# StearnsMTvrs.net
KiCad netlist of a schematic drawn in EAGLE
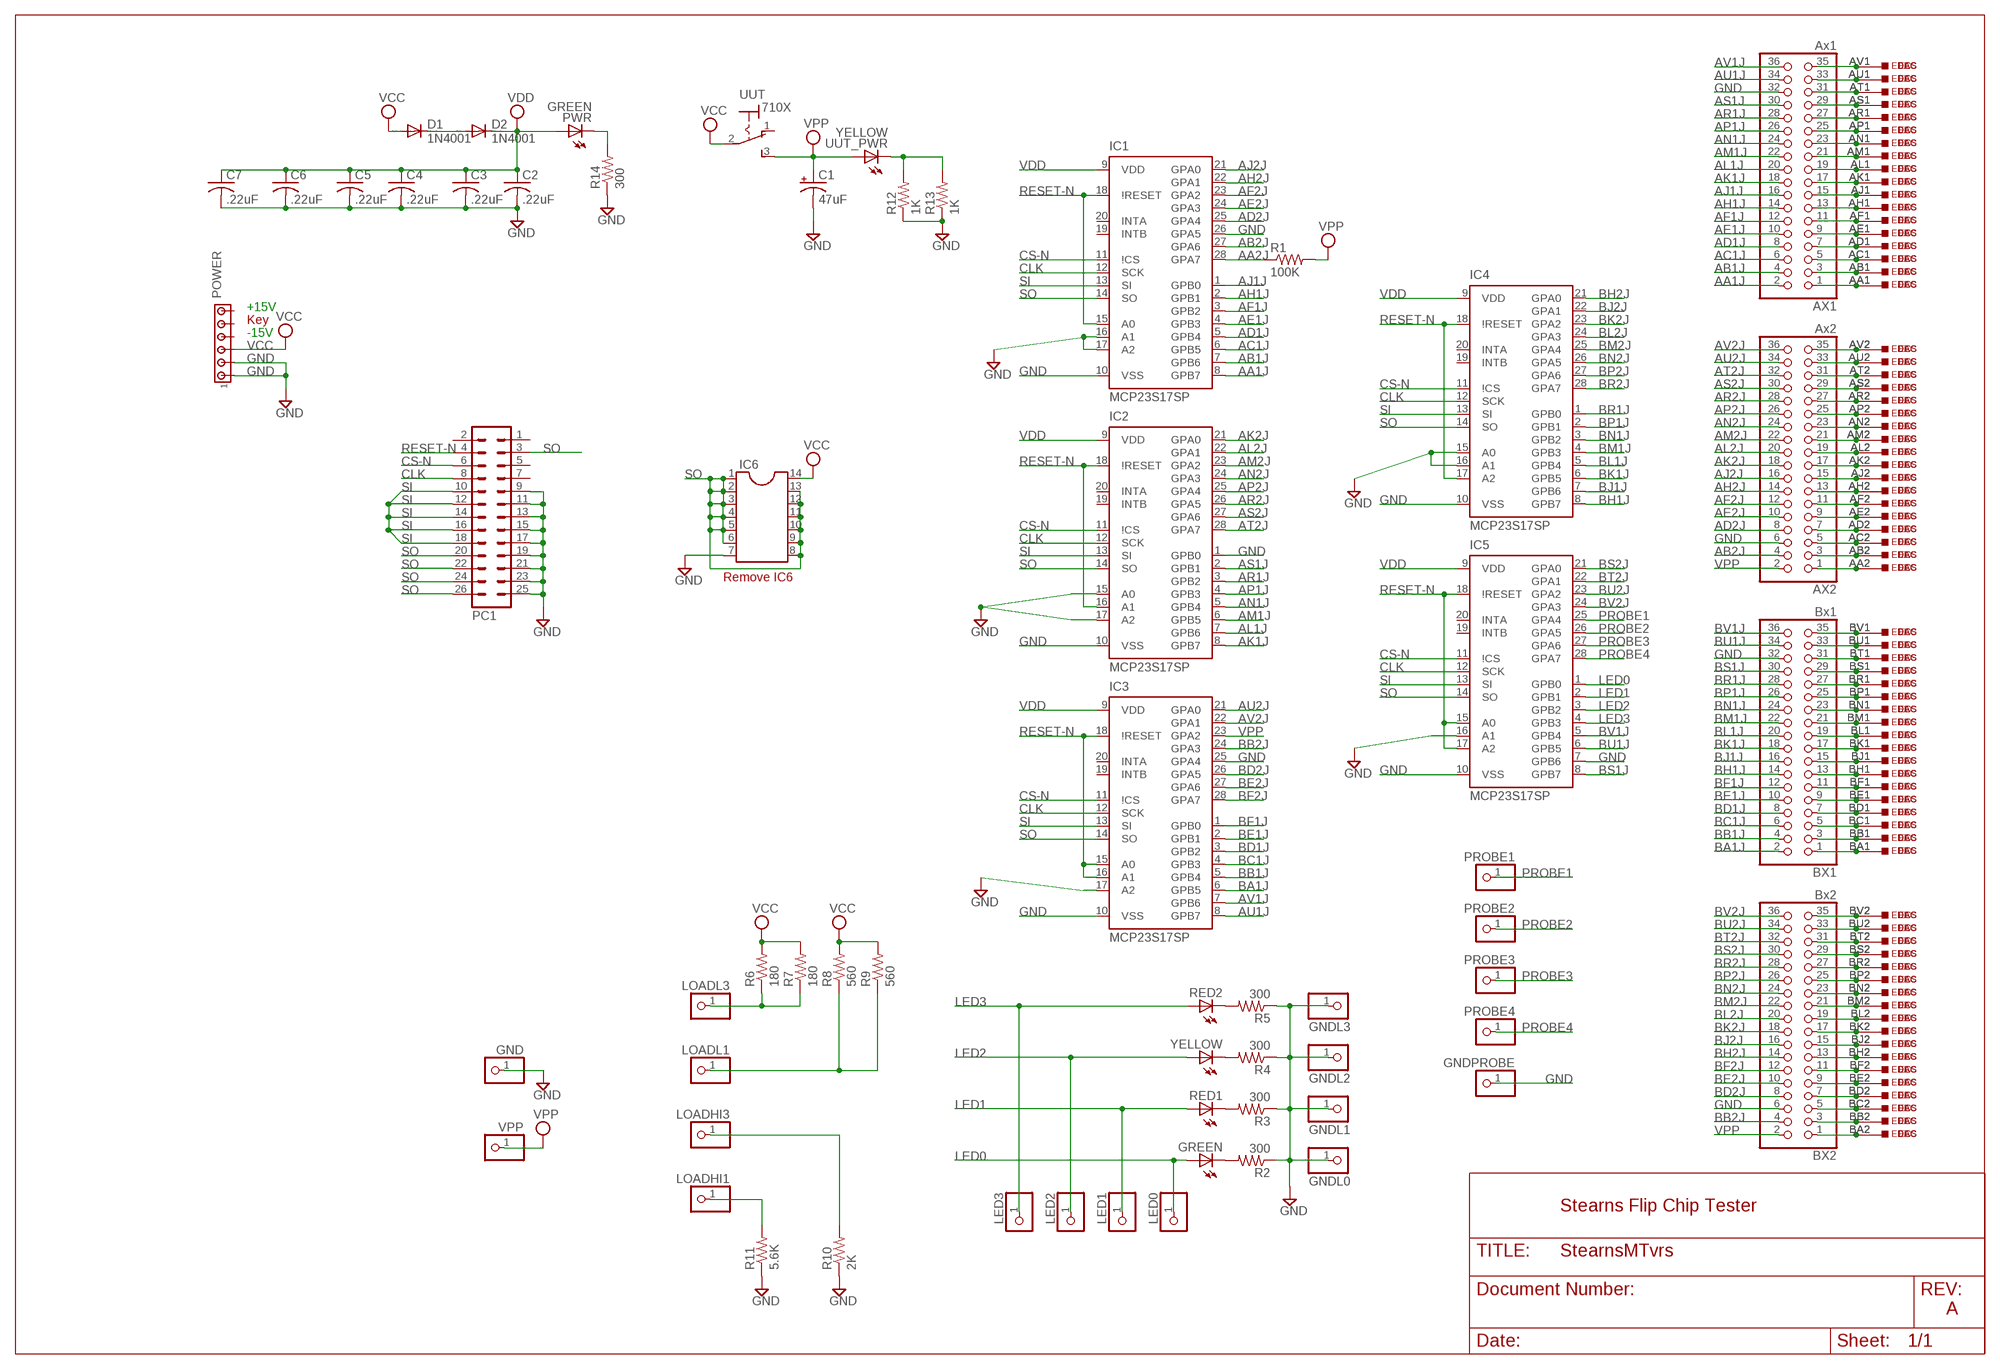
[diagram p0: schematic, sheet 1]

(export (version "E")
  (design (tool "Eeschema 10.0.6"))
  (components
    (comp (ref "AX1")
      (value "Ax1")
      (footprint "eagle-import:2X18")
      (libsource (lib "eagle-import") (part "PINHD-2X18"))
    )
    (comp (ref "AX2")
      (value "Ax2")
      (footprint "eagle-import:2X18")
      (libsource (lib "eagle-import") (part "PINHD-2X18"))
    )
    (comp (ref "BX1")
      (value "Bx1")
      (footprint "eagle-import:2X18")
      (libsource (lib "eagle-import") (part "PINHD-2X18"))
    )
    (comp (ref "BX2")
      (value "Bx2")
      (footprint "eagle-import:2X18")
      (libsource (lib "eagle-import") (part "PINHD-2X18"))
    )
    (comp (ref "C1")
      (value "47uF")
      (footprint "eagle-import:E5-8,5")
      (libsource (lib "eagle-import") (part "CPOL-USE5-8.5"))
    )
    (comp (ref "C2")
      (value ".22uF")
      (footprint "eagle-import:C050-025X075")
      (libsource (lib "eagle-import") (part "C-US050-025X075"))
    )
    (comp (ref "C3")
      (value ".22uF")
      (footprint "eagle-import:C050-025X075")
      (libsource (lib "eagle-import") (part "C-US050-025X075"))
    )
    (comp (ref "C4")
      (value ".22uF")
      (footprint "eagle-import:C050-025X075")
      (libsource (lib "eagle-import") (part "C-US050-025X075"))
    )
    (comp (ref "C5")
      (value ".22uF")
      (footprint "eagle-import:C050-025X075")
      (libsource (lib "eagle-import") (part "C-US050-025X075"))
    )
    (comp (ref "C6")
      (value ".22uF")
      (footprint "eagle-import:C050-025X075")
      (libsource (lib "eagle-import") (part "C-US050-025X075"))
    )
    (comp (ref "C7")
      (value ".22uF")
      (footprint "eagle-import:C050-025X075")
      (libsource (lib "eagle-import") (part "C-US050-025X075"))
    )
    (comp (ref "D1")
      (value "1N4001")
      (footprint "eagle-import:DO41-10")
      (libsource (lib "eagle-import") (part "1N4004"))
    )
    (comp (ref "D2")
      (value "1N4001")
      (footprint "eagle-import:DO41-10")
      (libsource (lib "eagle-import") (part "1N4004"))
    )
    (comp (ref "DEC")
      (value "W971")
      (footprint "eagle-import:H807-2")
      (libsource (lib "eagle-import") (part "W971"))
    )
    (comp (ref "ECS")
      (value "W971ECS")
      (footprint "eagle-import:ECS2418-2")
      (libsource (lib "eagle-import") (part "W971ECS"))
    )
    (comp (ref "EDAC")
      (value "W971EDAC")
      (footprint "eagle-import:EDAC346-36-2")
      (libsource (lib "eagle-import") (part "W971EDAC"))
    )
    (comp (ref "GND")
      (value "PINHD-1X1")
      (footprint "eagle-import:1X01")
      (libsource (lib "eagle-import") (part "PINHD-1X1"))
    )
    (comp (ref "GNDL0")
      (value "PINHD-1X1")
      (footprint "eagle-import:1X01")
      (libsource (lib "eagle-import") (part "PINHD-1X1"))
    )
    (comp (ref "GNDL1")
      (value "PINHD-1X1")
      (footprint "eagle-import:1X01")
      (libsource (lib "eagle-import") (part "PINHD-1X1"))
    )
    (comp (ref "GNDL2")
      (value "PINHD-1X1")
      (footprint "eagle-import:1X01")
      (libsource (lib "eagle-import") (part "PINHD-1X1"))
    )
    (comp (ref "GNDL3")
      (value "PINHD-1X1")
      (footprint "eagle-import:1X01")
      (libsource (lib "eagle-import") (part "PINHD-1X1"))
    )
    (comp (ref "GNDPROBE")
      (value "PINHD-1X1")
      (footprint "eagle-import:1X01")
      (libsource (lib "eagle-import") (part "PINHD-1X1"))
    )
    (comp (ref "GREEN")
      (value "LED5MM")
      (footprint "eagle-import:LED5MM")
      (libsource (lib "eagle-import") (part "LED5MM"))
    )
    (comp (ref "IC1")
      (value "MCP23S17SP")
      (footprint "eagle-import:DIL28-3")
      (libsource (lib "eagle-import") (part "MCP23S17SP"))
    )
    (comp (ref "IC2")
      (value "MCP23S17SP")
      (footprint "eagle-import:DIL28-3")
      (libsource (lib "eagle-import") (part "MCP23S17SP"))
    )
    (comp (ref "IC3")
      (value "MCP23S17SP")
      (footprint "eagle-import:DIL28-3")
      (libsource (lib "eagle-import") (part "MCP23S17SP"))
    )
    (comp (ref "IC4")
      (value "MCP23S17SP")
      (footprint "eagle-import:DIL28-3")
      (libsource (lib "eagle-import") (part "MCP23S17SP"))
    )
    (comp (ref "IC5")
      (value "MCP23S17SP")
      (footprint "eagle-import:DIL28-3")
      (libsource (lib "eagle-import") (part "MCP23S17SP"))
    )
    (comp (ref "IC6")
      (value "DIL14")
      (footprint "eagle-import:DIL14")
      (libsource (lib "eagle-import") (part "DIL14"))
    )
    (comp (ref "LED0")
      (value "PINHD-1X1")
      (footprint "eagle-import:1X01")
      (libsource (lib "eagle-import") (part "PINHD-1X1"))
    )
    (comp (ref "LED1")
      (value "PINHD-1X1")
      (footprint "eagle-import:1X01")
      (libsource (lib "eagle-import") (part "PINHD-1X1"))
    )
    (comp (ref "LED2")
      (value "PINHD-1X1")
      (footprint "eagle-import:1X01")
      (libsource (lib "eagle-import") (part "PINHD-1X1"))
    )
    (comp (ref "LED3")
      (value "PINHD-1X1")
      (footprint "eagle-import:1X01")
      (libsource (lib "eagle-import") (part "PINHD-1X1"))
    )
    (comp (ref "LOADHI1")
      (value "PINHD-1X1")
      (footprint "eagle-import:1X01")
      (libsource (lib "eagle-import") (part "PINHD-1X1"))
    )
    (comp (ref "LOADHI3")
      (value "PINHD-1X1")
      (footprint "eagle-import:1X01")
      (libsource (lib "eagle-import") (part "PINHD-1X1"))
    )
    (comp (ref "LOADL1")
      (value "PINHD-1X1")
      (footprint "eagle-import:1X01")
      (libsource (lib "eagle-import") (part "PINHD-1X1"))
    )
    (comp (ref "LOADL3")
      (value "PINHD-1X1")
      (footprint "eagle-import:1X01")
      (libsource (lib "eagle-import") (part "PINHD-1X1"))
    )
    (comp (ref "PC1")
      (value "MA13-2")
      (footprint "eagle-import:MA13-2")
      (libsource (lib "eagle-import") (part "MA13-2"))
    )
    (comp (ref "POWER")
      (value "MTA06-156")
      (footprint "eagle-import:1X6MTA")
      (libsource (lib "eagle-import") (part "MTA06-156"))
    )
    (comp (ref "PROBE1")
      (value "PINHD-1X1")
      (footprint "eagle-import:1X01")
      (libsource (lib "eagle-import") (part "PINHD-1X1"))
    )
    (comp (ref "PROBE2")
      (value "PINHD-1X1")
      (footprint "eagle-import:1X01")
      (libsource (lib "eagle-import") (part "PINHD-1X1"))
    )
    (comp (ref "PROBE3")
      (value "PINHD-1X1")
      (footprint "eagle-import:1X01")
      (libsource (lib "eagle-import") (part "PINHD-1X1"))
    )
    (comp (ref "PROBE4")
      (value "PINHD-1X1")
      (footprint "eagle-import:1X01")
      (libsource (lib "eagle-import") (part "PINHD-1X1"))
    )
    (comp (ref "PWR")
      (value "GREEN")
      (footprint "eagle-import:LED5MM")
      (libsource (lib "eagle-import") (part "LED5MM"))
    )
    (comp (ref "R1")
      (value "100K")
      (footprint "eagle-import:0207_10")
      (libsource (lib "eagle-import") (part "R-US_0207/10"))
    )
    (comp (ref "R2")
      (value "300")
      (footprint "eagle-import:0207_10")
      (libsource (lib "eagle-import") (part "R-US_0207/10"))
    )
    (comp (ref "R3")
      (value "300")
      (footprint "eagle-import:0207_10")
      (libsource (lib "eagle-import") (part "R-US_0207/10"))
    )
    (comp (ref "R4")
      (value "300")
      (footprint "eagle-import:0207_10")
      (libsource (lib "eagle-import") (part "R-US_0207/10"))
    )
    (comp (ref "R5")
      (value "300")
      (footprint "eagle-import:0207_10")
      (libsource (lib "eagle-import") (part "R-US_0207/10"))
    )
    (comp (ref "R6")
      (value "180")
      (footprint "eagle-import:0207_10")
      (libsource (lib "eagle-import") (part "R-US_0207/10"))
    )
    (comp (ref "R7")
      (value "180")
      (footprint "eagle-import:0207_10")
      (libsource (lib "eagle-import") (part "R-US_0207/10"))
    )
    (comp (ref "R8")
      (value "560")
      (footprint "eagle-import:0207_10")
      (libsource (lib "eagle-import") (part "R-US_0207/10"))
    )
    (comp (ref "R9")
      (value "560")
      (footprint "eagle-import:0207_10")
      (libsource (lib "eagle-import") (part "R-US_0207/10"))
    )
    (comp (ref "R10")
      (value "2K")
      (footprint "eagle-import:0207_10")
      (libsource (lib "eagle-import") (part "R-US_0207/10"))
    )
    (comp (ref "R11")
      (value "5.6K")
      (footprint "eagle-import:0207_10")
      (libsource (lib "eagle-import") (part "R-US_0207/10"))
    )
    (comp (ref "R12")
      (value "1K")
      (footprint "eagle-import:0207_10")
      (libsource (lib "eagle-import") (part "R-US_0207/10"))
    )
    (comp (ref "R13")
      (value "1K")
      (footprint "eagle-import:0207_10")
      (libsource (lib "eagle-import") (part "R-US_0207/10"))
    )
    (comp (ref "R14")
      (value "300")
      (footprint "eagle-import:0207_10")
      (libsource (lib "eagle-import") (part "R-US_0207/10"))
    )
    (comp (ref "RED1")
      (value "LED5MM")
      (footprint "eagle-import:LED5MM")
      (libsource (lib "eagle-import") (part "LED5MM"))
    )
    (comp (ref "RED2")
      (value "LED5MM")
      (footprint "eagle-import:LED5MM")
      (libsource (lib "eagle-import") (part "LED5MM"))
    )
    (comp (ref "UUT")
      (value "710X")
      (footprint "eagle-import:7109MD9V3")
      (libsource (lib "eagle-import") (part "710X"))
    )
    (comp (ref "UUT_PWR")
      (value "YELLOW")
      (footprint "eagle-import:LED5MM")
      (libsource (lib "eagle-import") (part "LED5MM"))
    )
    (comp (ref "VPP")
      (value "PINHD-1X1")
      (footprint "eagle-import:1X01")
      (libsource (lib "eagle-import") (part "PINHD-1X1"))
    )
    (comp (ref "YELLOW")
      (value "LED5MM")
      (footprint "eagle-import:LED5MM")
      (libsource (lib "eagle-import") (part "LED5MM"))
    )
  )
  (nets
    (net (code "1") (name "/AA1J") (class "Default")
      (node (ref "AX1") (pin "2") (pinfunction "2_2") (pintype "passive"))
      (node (ref "IC1") (pin "8") (pinfunction "GPB7_8") (pintype "bidirectional"))
    )
    (net (code "2") (name "/AA2J") (class "Default")
      (node (ref "IC1") (pin "28") (pinfunction "GPA7_28") (pintype "bidirectional"))
      (node (ref "R1") (pin "1") (pinfunction "1_1") (pintype "passive"))
    )
    (net (code "3") (name "/AB1J") (class "Default")
      (node (ref "AX1") (pin "4") (pinfunction "4_4") (pintype "passive"))
      (node (ref "IC1") (pin "7") (pinfunction "GPB6_7") (pintype "bidirectional"))
    )
    (net (code "4") (name "/AB2J") (class "Default")
      (node (ref "AX2") (pin "4") (pinfunction "4_4") (pintype "passive"))
      (node (ref "IC1") (pin "27") (pinfunction "GPA6_27") (pintype "bidirectional"))
    )
    (net (code "5") (name "/AC1J") (class "Default")
      (node (ref "AX1") (pin "6") (pinfunction "6_6") (pintype "passive"))
      (node (ref "IC1") (pin "6") (pinfunction "GPB5_6") (pintype "bidirectional"))
    )
    (net (code "6") (name "/AD1J") (class "Default")
      (node (ref "AX1") (pin "8") (pinfunction "8_8") (pintype "passive"))
      (node (ref "IC1") (pin "5") (pinfunction "GPB4_5") (pintype "bidirectional"))
    )
    (net (code "7") (name "/AD2J") (class "Default")
      (node (ref "AX2") (pin "8") (pinfunction "8_8") (pintype "passive"))
      (node (ref "IC1") (pin "25") (pinfunction "GPA4_25") (pintype "bidirectional"))
    )
    (net (code "8") (name "/AE1J") (class "Default")
      (node (ref "AX1") (pin "10") (pinfunction "10_10") (pintype "passive"))
      (node (ref "IC1") (pin "4") (pinfunction "GPB3_4") (pintype "bidirectional"))
    )
    (net (code "9") (name "/AE2J") (class "Default")
      (node (ref "AX2") (pin "10") (pinfunction "10_10") (pintype "passive"))
      (node (ref "IC1") (pin "24") (pinfunction "GPA3_24") (pintype "bidirectional"))
    )
    (net (code "10") (name "/AF1J") (class "Default")
      (node (ref "AX1") (pin "12") (pinfunction "12_12") (pintype "passive"))
      (node (ref "IC1") (pin "3") (pinfunction "GPB2_3") (pintype "bidirectional"))
    )
    (net (code "11") (name "/AF2J") (class "Default")
      (node (ref "AX2") (pin "12") (pinfunction "12_12") (pintype "passive"))
      (node (ref "IC1") (pin "23") (pinfunction "GPA2_23") (pintype "bidirectional"))
    )
    (net (code "12") (name "/AH1J") (class "Default")
      (node (ref "AX1") (pin "14") (pinfunction "14_14") (pintype "passive"))
      (node (ref "IC1") (pin "2") (pinfunction "GPB1_2") (pintype "bidirectional"))
    )
    (net (code "13") (name "/AH2J") (class "Default")
      (node (ref "AX2") (pin "14") (pinfunction "14_14") (pintype "passive"))
      (node (ref "IC1") (pin "22") (pinfunction "GPA1_22") (pintype "bidirectional"))
    )
    (net (code "14") (name "/AJ1J") (class "Default")
      (node (ref "AX1") (pin "16") (pinfunction "16_16") (pintype "passive"))
      (node (ref "IC1") (pin "1") (pinfunction "GPB0_1") (pintype "bidirectional"))
    )
    (net (code "15") (name "/AJ2J") (class "Default")
      (node (ref "AX2") (pin "16") (pinfunction "16_16") (pintype "passive"))
      (node (ref "IC1") (pin "21") (pinfunction "GPA0_21") (pintype "bidirectional"))
    )
    (net (code "16") (name "/AK1J") (class "Default")
      (node (ref "AX1") (pin "18") (pinfunction "18_18") (pintype "passive"))
      (node (ref "IC2") (pin "8") (pinfunction "GPB7_8") (pintype "bidirectional"))
    )
    (net (code "17") (name "/AK2J") (class "Default")
      (node (ref "AX2") (pin "18") (pinfunction "18_18") (pintype "passive"))
      (node (ref "IC2") (pin "21") (pinfunction "GPA0_21") (pintype "bidirectional"))
    )
    (net (code "18") (name "/AL1J") (class "Default")
      (node (ref "AX1") (pin "20") (pinfunction "20_20") (pintype "passive"))
      (node (ref "IC2") (pin "7") (pinfunction "GPB6_7") (pintype "bidirectional"))
    )
    (net (code "19") (name "/AL2J") (class "Default")
      (node (ref "AX2") (pin "20") (pinfunction "20_20") (pintype "passive"))
      (node (ref "IC2") (pin "22") (pinfunction "GPA1_22") (pintype "bidirectional"))
    )
    (net (code "20") (name "/AM1J") (class "Default")
      (node (ref "AX1") (pin "22") (pinfunction "22_22") (pintype "passive"))
      (node (ref "IC2") (pin "6") (pinfunction "GPB5_6") (pintype "bidirectional"))
    )
    (net (code "21") (name "/AM2J") (class "Default")
      (node (ref "AX2") (pin "22") (pinfunction "22_22") (pintype "passive"))
      (node (ref "IC2") (pin "23") (pinfunction "GPA2_23") (pintype "bidirectional"))
    )
    (net (code "22") (name "/AN1J") (class "Default")
      (node (ref "AX1") (pin "24") (pinfunction "24_24") (pintype "passive"))
      (node (ref "IC2") (pin "5") (pinfunction "GPB4_5") (pintype "bidirectional"))
    )
    (net (code "23") (name "/AN2J") (class "Default")
      (node (ref "AX2") (pin "24") (pinfunction "24_24") (pintype "passive"))
      (node (ref "IC2") (pin "24") (pinfunction "GPA3_24") (pintype "bidirectional"))
    )
    (net (code "24") (name "/AP1J") (class "Default")
      (node (ref "AX1") (pin "26") (pinfunction "26_26") (pintype "passive"))
      (node (ref "IC2") (pin "4") (pinfunction "GPB3_4") (pintype "bidirectional"))
    )
    (net (code "25") (name "/AP2J") (class "Default")
      (node (ref "AX2") (pin "26") (pinfunction "26_26") (pintype "passive"))
      (node (ref "IC2") (pin "25") (pinfunction "GPA4_25") (pintype "bidirectional"))
    )
    (net (code "26") (name "/AR1J") (class "Default")
      (node (ref "AX1") (pin "28") (pinfunction "28_28") (pintype "passive"))
      (node (ref "IC2") (pin "3") (pinfunction "GPB2_3") (pintype "bidirectional"))
    )
    (net (code "27") (name "/AR2J") (class "Default")
      (node (ref "AX2") (pin "28") (pinfunction "28_28") (pintype "passive"))
      (node (ref "IC2") (pin "26") (pinfunction "GPA5_26") (pintype "bidirectional"))
    )
    (net (code "28") (name "/AS1J") (class "Default")
      (node (ref "AX1") (pin "30") (pinfunction "30_30") (pintype "passive"))
      (node (ref "IC2") (pin "2") (pinfunction "GPB1_2") (pintype "bidirectional"))
    )
    (net (code "29") (name "/AS2J") (class "Default")
      (node (ref "AX2") (pin "30") (pinfunction "30_30") (pintype "passive"))
      (node (ref "IC2") (pin "27") (pinfunction "GPA6_27") (pintype "bidirectional"))
    )
    (net (code "30") (name "/AT2J") (class "Default")
      (node (ref "AX2") (pin "32") (pinfunction "32_32") (pintype "passive"))
      (node (ref "IC2") (pin "28") (pinfunction "GPA7_28") (pintype "bidirectional"))
    )
    (net (code "31") (name "/AU1J") (class "Default")
      (node (ref "AX1") (pin "34") (pinfunction "34_34") (pintype "passive"))
      (node (ref "IC3") (pin "8") (pinfunction "GPB7_8") (pintype "bidirectional"))
    )
    (net (code "32") (name "/AU2J") (class "Default")
      (node (ref "AX2") (pin "34") (pinfunction "34_34") (pintype "passive"))
      (node (ref "IC3") (pin "21") (pinfunction "GPA0_21") (pintype "bidirectional"))
    )
    (net (code "33") (name "/AV1J") (class "Default")
      (node (ref "AX1") (pin "36") (pinfunction "36_36") (pintype "passive"))
      (node (ref "IC3") (pin "7") (pinfunction "GPB6_7") (pintype "bidirectional"))
    )
    (net (code "34") (name "/AV2J") (class "Default")
      (node (ref "AX2") (pin "36") (pinfunction "36_36") (pintype "passive"))
      (node (ref "IC3") (pin "22") (pinfunction "GPA1_22") (pintype "bidirectional"))
    )
    (net (code "35") (name "/BA1J") (class "Default")
      (node (ref "BX1") (pin "2") (pinfunction "2_2") (pintype "passive"))
      (node (ref "IC3") (pin "6") (pinfunction "GPB5_6") (pintype "bidirectional"))
    )
    (net (code "36") (name "/BB1J") (class "Default")
      (node (ref "BX1") (pin "4") (pinfunction "4_4") (pintype "passive"))
      (node (ref "IC3") (pin "5") (pinfunction "GPB4_5") (pintype "bidirectional"))
    )
    (net (code "37") (name "/BB2J") (class "Default")
      (node (ref "BX2") (pin "4") (pinfunction "4_4") (pintype "passive"))
      (node (ref "IC3") (pin "24") (pinfunction "GPA3_24") (pintype "bidirectional"))
    )
    (net (code "38") (name "/BC1J") (class "Default")
      (node (ref "BX1") (pin "6") (pinfunction "6_6") (pintype "passive"))
      (node (ref "IC3") (pin "4") (pinfunction "GPB3_4") (pintype "bidirectional"))
    )
    (net (code "39") (name "/BD1J") (class "Default")
      (node (ref "BX1") (pin "8") (pinfunction "8_8") (pintype "passive"))
      (node (ref "IC3") (pin "3") (pinfunction "GPB2_3") (pintype "bidirectional"))
    )
    (net (code "40") (name "/BD2J") (class "Default")
      (node (ref "BX2") (pin "8") (pinfunction "8_8") (pintype "passive"))
      (node (ref "IC3") (pin "26") (pinfunction "GPA5_26") (pintype "bidirectional"))
    )
    (net (code "41") (name "/BE1J") (class "Default")
      (node (ref "BX1") (pin "10") (pinfunction "10_10") (pintype "passive"))
      (node (ref "IC3") (pin "2") (pinfunction "GPB1_2") (pintype "bidirectional"))
    )
    (net (code "42") (name "/BE2J") (class "Default")
      (node (ref "BX2") (pin "10") (pinfunction "10_10") (pintype "passive"))
      (node (ref "IC3") (pin "27") (pinfunction "GPA6_27") (pintype "bidirectional"))
    )
    (net (code "43") (name "/BF1J") (class "Default")
      (node (ref "BX1") (pin "12") (pinfunction "12_12") (pintype "passive"))
      (node (ref "IC3") (pin "1") (pinfunction "GPB0_1") (pintype "bidirectional"))
    )
    (net (code "44") (name "/BF2J") (class "Default")
      (node (ref "BX2") (pin "12") (pinfunction "12_12") (pintype "passive"))
      (node (ref "IC3") (pin "28") (pinfunction "GPA7_28") (pintype "bidirectional"))
    )
    (net (code "45") (name "/BH1J") (class "Default")
      (node (ref "BX1") (pin "14") (pinfunction "14_14") (pintype "passive"))
      (node (ref "IC4") (pin "8") (pinfunction "GPB7_8") (pintype "bidirectional"))
    )
    (net (code "46") (name "/BH2J") (class "Default")
      (node (ref "BX2") (pin "14") (pinfunction "14_14") (pintype "passive"))
      (node (ref "IC4") (pin "21") (pinfunction "GPA0_21") (pintype "bidirectional"))
    )
    (net (code "47") (name "/BJ1J") (class "Default")
      (node (ref "BX1") (pin "16") (pinfunction "16_16") (pintype "passive"))
      (node (ref "IC4") (pin "7") (pinfunction "GPB6_7") (pintype "bidirectional"))
    )
    (net (code "48") (name "/BJ2J") (class "Default")
      (node (ref "BX2") (pin "16") (pinfunction "16_16") (pintype "passive"))
      (node (ref "IC4") (pin "22") (pinfunction "GPA1_22") (pintype "bidirectional"))
    )
    (net (code "49") (name "/BK1J") (class "Default")
      (node (ref "BX1") (pin "18") (pinfunction "18_18") (pintype "passive"))
      (node (ref "IC4") (pin "6") (pinfunction "GPB5_6") (pintype "bidirectional"))
    )
    (net (code "50") (name "/BK2J") (class "Default")
      (node (ref "BX2") (pin "18") (pinfunction "18_18") (pintype "passive"))
      (node (ref "IC4") (pin "23") (pinfunction "GPA2_23") (pintype "bidirectional"))
    )
    (net (code "51") (name "/BL1J") (class "Default")
      (node (ref "BX1") (pin "20") (pinfunction "20_20") (pintype "passive"))
      (node (ref "IC4") (pin "5") (pinfunction "GPB4_5") (pintype "bidirectional"))
    )
    (net (code "52") (name "/BL2J") (class "Default")
      (node (ref "BX2") (pin "20") (pinfunction "20_20") (pintype "passive"))
      (node (ref "IC4") (pin "24") (pinfunction "GPA3_24") (pintype "bidirectional"))
    )
    (net (code "53") (name "/BM1J") (class "Default")
      (node (ref "BX1") (pin "22") (pinfunction "22_22") (pintype "passive"))
      (node (ref "IC4") (pin "4") (pinfunction "GPB3_4") (pintype "bidirectional"))
    )
    (net (code "54") (name "/BM2J") (class "Default")
      (node (ref "BX2") (pin "22") (pinfunction "22_22") (pintype "passive"))
      (node (ref "IC4") (pin "25") (pinfunction "GPA4_25") (pintype "bidirectional"))
    )
    (net (code "55") (name "/BN1J") (class "Default")
      (node (ref "BX1") (pin "24") (pinfunction "24_24") (pintype "passive"))
      (node (ref "IC4") (pin "3") (pinfunction "GPB2_3") (pintype "bidirectional"))
    )
    (net (code "56") (name "/BN2J") (class "Default")
      (node (ref "BX2") (pin "24") (pinfunction "24_24") (pintype "passive"))
      (node (ref "IC4") (pin "26") (pinfunction "GPA5_26") (pintype "bidirectional"))
    )
    (net (code "57") (name "/BP1J") (class "Default")
      (node (ref "BX1") (pin "26") (pinfunction "26_26") (pintype "passive"))
      (node (ref "IC4") (pin "2") (pinfunction "GPB1_2") (pintype "bidirectional"))
    )
    (net (code "58") (name "/BP2J") (class "Default")
      (node (ref "BX2") (pin "26") (pinfunction "26_26") (pintype "passive"))
      (node (ref "IC4") (pin "27") (pinfunction "GPA6_27") (pintype "bidirectional"))
    )
    (net (code "59") (name "/BR1J") (class "Default")
      (node (ref "BX1") (pin "28") (pinfunction "28_28") (pintype "passive"))
      (node (ref "IC4") (pin "1") (pinfunction "GPB0_1") (pintype "bidirectional"))
    )
    (net (code "60") (name "/BR2J") (class "Default")
      (node (ref "BX2") (pin "28") (pinfunction "28_28") (pintype "passive"))
      (node (ref "IC4") (pin "28") (pinfunction "GPA7_28") (pintype "bidirectional"))
    )
    (net (code "61") (name "/BS1J") (class "Default")
      (node (ref "BX1") (pin "30") (pinfunction "30_30") (pintype "passive"))
      (node (ref "IC5") (pin "8") (pinfunction "GPB7_8") (pintype "bidirectional"))
    )
    (net (code "62") (name "/BS2J") (class "Default")
      (node (ref "BX2") (pin "30") (pinfunction "30_30") (pintype "passive"))
      (node (ref "IC5") (pin "21") (pinfunction "GPA0_21") (pintype "bidirectional"))
    )
    (net (code "63") (name "/BT2J") (class "Default")
      (node (ref "BX2") (pin "32") (pinfunction "32_32") (pintype "passive"))
      (node (ref "IC5") (pin "22") (pinfunction "GPA1_22") (pintype "bidirectional"))
    )
    (net (code "64") (name "/BU1J") (class "Default")
      (node (ref "BX1") (pin "34") (pinfunction "34_34") (pintype "passive"))
      (node (ref "IC5") (pin "6") (pinfunction "GPB5_6") (pintype "bidirectional"))
    )
    (net (code "65") (name "/BU2J") (class "Default")
      (node (ref "BX2") (pin "34") (pinfunction "34_34") (pintype "passive"))
      (node (ref "IC5") (pin "23") (pinfunction "GPA2_23") (pintype "bidirectional"))
    )
    (net (code "66") (name "/BV1J") (class "Default")
      (node (ref "BX1") (pin "36") (pinfunction "36_36") (pintype "passive"))
      (node (ref "IC5") (pin "5") (pinfunction "GPB4_5") (pintype "bidirectional"))
    )
    (net (code "67") (name "/BV2J") (class "Default")
      (node (ref "BX2") (pin "36") (pinfunction "36_36") (pintype "passive"))
      (node (ref "IC5") (pin "24") (pinfunction "GPA3_24") (pintype "bidirectional"))
    )
    (net (code "68") (name "/CLK") (class "Default")
      (node (ref "IC1") (pin "12") (pinfunction "SCK_12") (pintype "input"))
      (node (ref "IC2") (pin "12") (pinfunction "SCK_12") (pintype "input"))
      (node (ref "IC3") (pin "12") (pinfunction "SCK_12") (pintype "input"))
      (node (ref "IC4") (pin "12") (pinfunction "SCK_12") (pintype "input"))
      (node (ref "IC5") (pin "12") (pinfunction "SCK_12") (pintype "input"))
      (node (ref "PC1") (pin "8") (pinfunction "8_8") (pintype "passive"))
    )
    (net (code "69") (name "/CS-N") (class "Default")
      (node (ref "IC1") (pin "11") (pinfunction "\\~{CS}_11") (pintype "input"))
      (node (ref "IC2") (pin "11") (pinfunction "\\~{CS}_11") (pintype "input"))
      (node (ref "IC3") (pin "11") (pinfunction "\\~{CS}_11") (pintype "input"))
      (node (ref "IC4") (pin "11") (pinfunction "\\~{CS}_11") (pintype "input"))
      (node (ref "IC5") (pin "11") (pinfunction "\\~{CS}_11") (pintype "input"))
      (node (ref "PC1") (pin "6") (pinfunction "6_6") (pintype "passive"))
    )
    (net (code "70") (name "/LED0") (class "Default")
      (node (ref "GREEN") (pin "A") (pinfunction "A_A") (pintype "passive"))
      (node (ref "IC5") (pin "1") (pinfunction "GPB0_1") (pintype "bidirectional"))
      (node (ref "LED0") (pin "1") (pinfunction "1_1") (pintype "passive"))
    )
    (net (code "71") (name "/LED1") (class "Default")
      (node (ref "IC5") (pin "2") (pinfunction "GPB1_2") (pintype "bidirectional"))
      (node (ref "LED1") (pin "1") (pinfunction "1_1") (pintype "passive"))
      (node (ref "RED1") (pin "A") (pinfunction "A_A") (pintype "passive"))
    )
    (net (code "72") (name "/LED2") (class "Default")
      (node (ref "IC5") (pin "3") (pinfunction "GPB2_3") (pintype "bidirectional"))
      (node (ref "LED2") (pin "1") (pinfunction "1_1") (pintype "passive"))
      (node (ref "YELLOW") (pin "A") (pinfunction "A_A") (pintype "passive"))
    )
    (net (code "73") (name "/LED3") (class "Default")
      (node (ref "IC5") (pin "4") (pinfunction "GPB3_4") (pintype "bidirectional"))
      (node (ref "LED3") (pin "1") (pinfunction "1_1") (pintype "passive"))
      (node (ref "RED2") (pin "A") (pinfunction "A_A") (pintype "passive"))
    )
    (net (code "74") (name "/PROBE1") (class "Default")
      (node (ref "IC5") (pin "25") (pinfunction "GPA4_25") (pintype "bidirectional"))
      (node (ref "PROBE1") (pin "1") (pinfunction "1_1") (pintype "passive"))
    )
    (net (code "75") (name "/PROBE2") (class "Default")
      (node (ref "IC5") (pin "26") (pinfunction "GPA5_26") (pintype "bidirectional"))
      (node (ref "PROBE2") (pin "1") (pinfunction "1_1") (pintype "passive"))
    )
    (net (code "76") (name "/PROBE3") (class "Default")
      (node (ref "IC5") (pin "27") (pinfunction "GPA6_27") (pintype "bidirectional"))
      (node (ref "PROBE3") (pin "1") (pinfunction "1_1") (pintype "passive"))
    )
    (net (code "77") (name "/PROBE4") (class "Default")
      (node (ref "IC5") (pin "28") (pinfunction "GPA7_28") (pintype "bidirectional"))
      (node (ref "PROBE4") (pin "1") (pinfunction "1_1") (pintype "passive"))
    )
    (net (code "78") (name "/RESET-N") (class "Default")
      (node (ref "IC1") (pin "15") (pinfunction "A0_15") (pintype "input"))
      (node (ref "IC1") (pin "18") (pinfunction "\\~{RESET}_18") (pintype "input"))
      (node (ref "IC2") (pin "16") (pinfunction "A1_16") (pintype "input"))
      (node (ref "IC2") (pin "18") (pinfunction "\\~{RESET}_18") (pintype "input"))
      (node (ref "IC3") (pin "15") (pinfunction "A0_15") (pintype "input"))
      (node (ref "IC3") (pin "16") (pinfunction "A1_16") (pintype "input"))
      (node (ref "IC3") (pin "18") (pinfunction "\\~{RESET}_18") (pintype "input"))
      (node (ref "IC4") (pin "17") (pinfunction "A2_17") (pintype "input"))
      (node (ref "IC4") (pin "18") (pinfunction "\\~{RESET}_18") (pintype "input"))
      (node (ref "IC5") (pin "15") (pinfunction "A0_15") (pintype "input"))
      (node (ref "IC5") (pin "17") (pinfunction "A2_17") (pintype "input"))
      (node (ref "IC5") (pin "18") (pinfunction "\\~{RESET}_18") (pintype "input"))
      (node (ref "PC1") (pin "4") (pinfunction "4_4") (pintype "passive"))
    )
    (net (code "79") (name "/SI") (class "Default")
      (node (ref "IC1") (pin "13") (pinfunction "SI_13") (pintype "input"))
      (node (ref "IC2") (pin "13") (pinfunction "SI_13") (pintype "input"))
      (node (ref "IC3") (pin "13") (pinfunction "SI_13") (pintype "input"))
      (node (ref "IC4") (pin "13") (pinfunction "SI_13") (pintype "input"))
      (node (ref "IC5") (pin "13") (pinfunction "SI_13") (pintype "input"))
      (node (ref "PC1") (pin "10") (pinfunction "10_10") (pintype "passive"))
      (node (ref "PC1") (pin "12") (pinfunction "12_12") (pintype "passive"))
      (node (ref "PC1") (pin "14") (pinfunction "14_14") (pintype "passive"))
      (node (ref "PC1") (pin "16") (pinfunction "16_16") (pintype "passive"))
      (node (ref "PC1") (pin "18") (pinfunction "18_18") (pintype "passive"))
    )
    (net (code "80") (name "/SO") (class "Default")
      (node (ref "IC1") (pin "14") (pinfunction "SO_14") (pintype "output"))
      (node (ref "IC2") (pin "14") (pinfunction "SO_14") (pintype "output"))
      (node (ref "IC3") (pin "14") (pinfunction "SO_14") (pintype "output"))
      (node (ref "IC4") (pin "14") (pinfunction "SO_14") (pintype "output"))
      (node (ref "IC5") (pin "14") (pinfunction "SO_14") (pintype "output"))
      (node (ref "IC6") (pin "1") (pinfunction "1_1") (pintype "passive"))
      (node (ref "IC6") (pin "10") (pinfunction "10_10") (pintype "passive"))
      (node (ref "IC6") (pin "11") (pinfunction "11_11") (pintype "passive"))
      (node (ref "IC6") (pin "12") (pinfunction "12_12") (pintype "passive"))
      (node (ref "IC6") (pin "13") (pinfunction "13_13") (pintype "passive"))
      (node (ref "IC6") (pin "2") (pinfunction "2_2") (pintype "passive"))
      (node (ref "IC6") (pin "3") (pinfunction "3_3") (pintype "passive"))
      (node (ref "IC6") (pin "4") (pinfunction "4_4") (pintype "passive"))
      (node (ref "IC6") (pin "5") (pinfunction "5_5") (pintype "passive"))
      (node (ref "IC6") (pin "6") (pinfunction "6_6") (pintype "passive"))
      (node (ref "IC6") (pin "8") (pinfunction "8_8") (pintype "passive"))
      (node (ref "IC6") (pin "9") (pinfunction "9_9") (pintype "passive"))
      (node (ref "PC1") (pin "20") (pinfunction "20_20") (pintype "passive"))
      (node (ref "PC1") (pin "22") (pinfunction "22_22") (pintype "passive"))
      (node (ref "PC1") (pin "24") (pinfunction "24_24") (pintype "passive"))
      (node (ref "PC1") (pin "26") (pinfunction "26_26") (pintype "passive"))
      (node (ref "PC1") (pin "3") (pinfunction "3_3") (pintype "passive"))
    )
    (net (code "81") (name "GND") (class "Default")
      (node (ref "AX1") (pin "32") (pinfunction "32_32") (pintype "passive"))
      (node (ref "AX2") (pin "6") (pinfunction "6_6") (pintype "passive"))
      (node (ref "BX1") (pin "32") (pinfunction "32_32") (pintype "passive"))
      (node (ref "BX2") (pin "6") (pinfunction "6_6") (pintype "passive"))
      (node (ref "C1") (pin "-") (pinfunction "-_-") (pintype "passive"))
      (node (ref "C2") (pin "2") (pinfunction "2_2") (pintype "passive"))
      (node (ref "C3") (pin "2") (pinfunction "2_2") (pintype "passive"))
      (node (ref "C4") (pin "2") (pinfunction "2_2") (pintype "passive"))
      (node (ref "C5") (pin "2") (pinfunction "2_2") (pintype "passive"))
      (node (ref "C6") (pin "2") (pinfunction "2_2") (pintype "passive"))
      (node (ref "C7") (pin "2") (pinfunction "2_2") (pintype "passive"))
      (node (ref "GND") (pin "1") (pinfunction "1_1") (pintype "passive"))
      (node (ref "GNDL0") (pin "1") (pinfunction "1_1") (pintype "passive"))
      (node (ref "GNDL1") (pin "1") (pinfunction "1_1") (pintype "passive"))
      (node (ref "GNDL2") (pin "1") (pinfunction "1_1") (pintype "passive"))
      (node (ref "GNDL3") (pin "1") (pinfunction "1_1") (pintype "passive"))
      (node (ref "GNDPROBE") (pin "1") (pinfunction "1_1") (pintype "passive"))
      (node (ref "IC1") (pin "10") (pinfunction "VSS_10") (pintype "power_in"))
      (node (ref "IC1") (pin "16") (pinfunction "A1_16") (pintype "input"))
      (node (ref "IC1") (pin "17") (pinfunction "A2_17") (pintype "input"))
      (node (ref "IC1") (pin "26") (pinfunction "GPA5_26") (pintype "bidirectional"))
      (node (ref "IC2") (pin "1") (pinfunction "GPB0_1") (pintype "bidirectional"))
      (node (ref "IC2") (pin "10") (pinfunction "VSS_10") (pintype "power_in"))
      (node (ref "IC2") (pin "15") (pinfunction "A0_15") (pintype "input"))
      (node (ref "IC2") (pin "17") (pinfunction "A2_17") (pintype "input"))
      (node (ref "IC3") (pin "10") (pinfunction "VSS_10") (pintype "power_in"))
      (node (ref "IC3") (pin "17") (pinfunction "A2_17") (pintype "input"))
      (node (ref "IC3") (pin "25") (pinfunction "GPA4_25") (pintype "bidirectional"))
      (node (ref "IC4") (pin "10") (pinfunction "VSS_10") (pintype "power_in"))
      (node (ref "IC4") (pin "15") (pinfunction "A0_15") (pintype "input"))
      (node (ref "IC4") (pin "16") (pinfunction "A1_16") (pintype "input"))
      (node (ref "IC5") (pin "10") (pinfunction "VSS_10") (pintype "power_in"))
      (node (ref "IC5") (pin "16") (pinfunction "A1_16") (pintype "input"))
      (node (ref "IC5") (pin "7") (pinfunction "GPB6_7") (pintype "bidirectional"))
      (node (ref "IC6") (pin "7") (pinfunction "7_7") (pintype "passive"))
      (node (ref "PC1") (pin "11") (pinfunction "11_11") (pintype "passive"))
      (node (ref "PC1") (pin "13") (pinfunction "13_13") (pintype "passive"))
      (node (ref "PC1") (pin "15") (pinfunction "15_15") (pintype "passive"))
      (node (ref "PC1") (pin "17") (pinfunction "17_17") (pintype "passive"))
      (node (ref "PC1") (pin "19") (pinfunction "19_19") (pintype "passive"))
      (node (ref "PC1") (pin "21") (pinfunction "21_21") (pintype "passive"))
      (node (ref "PC1") (pin "23") (pinfunction "23_23") (pintype "passive"))
      (node (ref "PC1") (pin "25") (pinfunction "25_25") (pintype "passive"))
      (node (ref "PC1") (pin "9") (pinfunction "9_9") (pintype "passive"))
      (node (ref "POWER") (pin "1") (pinfunction "1_1") (pintype "passive"))
      (node (ref "POWER") (pin "2") (pinfunction "2_2") (pintype "passive"))
      (node (ref "R10") (pin "1") (pinfunction "1_1") (pintype "passive"))
      (node (ref "R11") (pin "1") (pinfunction "1_1") (pintype "passive"))
      (node (ref "R12") (pin "1") (pinfunction "1_1") (pintype "passive"))
      (node (ref "R13") (pin "1") (pinfunction "1_1") (pintype "passive"))
      (node (ref "R14") (pin "1") (pinfunction "1_1") (pintype "passive"))
      (node (ref "R2") (pin "1") (pinfunction "1_1") (pintype "passive"))
      (node (ref "R3") (pin "1") (pinfunction "1_1") (pintype "passive"))
      (node (ref "R4") (pin "1") (pinfunction "1_1") (pintype "passive"))
      (node (ref "R5") (pin "1") (pinfunction "1_1") (pintype "passive"))
    )
    (net (code "82") (name "Net-(D1-PadC)") (class "Default")
      (node (ref "D1") (pin "C") (pinfunction "C_C") (pintype "passive"))
      (node (ref "D2") (pin "A") (pinfunction "A_A") (pintype "passive"))
    )
    (net (code "83") (name "Net-(DECA-P$2)") (class "Default")
      (node (ref "AX1") (pin "1") (pinfunction "1_1") (pintype "passive"))
      (node (ref "DEC") (pin "AA1") (pinfunction "P$2_AA1") (pintype "bidirectional"))
      (node (ref "ECS") (pin "AA1") (pinfunction "P$2_AA1") (pintype "bidirectional"))
      (node (ref "EDAC") (pin "AA1") (pinfunction "P$2_AA1") (pintype "bidirectional"))
    )
    (net (code "84") (name "Net-(DECAA-P$2)") (class "Default")
      (node (ref "AX1") (pin "27") (pinfunction "27_27") (pintype "passive"))
      (node (ref "DEC") (pin "AR1") (pinfunction "P$2_AR1") (pintype "bidirectional"))
      (node (ref "ECS") (pin "AR1") (pinfunction "P$2_AR1") (pintype "bidirectional"))
      (node (ref "EDAC") (pin "AR1") (pinfunction "P$2_AR1") (pintype "bidirectional"))
    )
    (net (code "85") (name "Net-(DECAB-P$2)") (class "Default")
      (node (ref "AX2") (pin "27") (pinfunction "27_27") (pintype "passive"))
      (node (ref "DEC") (pin "AR2") (pinfunction "P$2_AR2") (pintype "bidirectional"))
      (node (ref "ECS") (pin "AR2") (pinfunction "P$2_AR2") (pintype "bidirectional"))
      (node (ref "EDAC") (pin "AR2") (pinfunction "P$2_AR2") (pintype "bidirectional"))
    )
    (net (code "86") (name "Net-(DECAC-P$2)") (class "Default")
      (node (ref "AX1") (pin "29") (pinfunction "29_29") (pintype "passive"))
      (node (ref "DEC") (pin "AS1") (pinfunction "P$2_AS1") (pintype "bidirectional"))
      (node (ref "ECS") (pin "AS1") (pinfunction "P$2_AS1") (pintype "bidirectional"))
      (node (ref "EDAC") (pin "AS1") (pinfunction "P$2_AS1") (pintype "bidirectional"))
    )
    (net (code "87") (name "Net-(DECAD-P$2)") (class "Default")
      (node (ref "AX2") (pin "29") (pinfunction "29_29") (pintype "passive"))
      (node (ref "DEC") (pin "AS2") (pinfunction "P$2_AS2") (pintype "bidirectional"))
      (node (ref "ECS") (pin "AS2") (pinfunction "P$2_AS2") (pintype "bidirectional"))
      (node (ref "EDAC") (pin "AS2") (pinfunction "P$2_AS2") (pintype "bidirectional"))
    )
    (net (code "88") (name "Net-(DECAE-P$2)") (class "Default")
      (node (ref "AX1") (pin "31") (pinfunction "31_31") (pintype "passive"))
      (node (ref "DEC") (pin "AT1") (pinfunction "P$2_AT1") (pintype "bidirectional"))
      (node (ref "ECS") (pin "AT1") (pinfunction "P$2_AT1") (pintype "bidirectional"))
      (node (ref "EDAC") (pin "AT1") (pinfunction "P$2_AT1") (pintype "bidirectional"))
    )
    (net (code "89") (name "Net-(DECAF-P$2)") (class "Default")
      (node (ref "AX2") (pin "31") (pinfunction "31_31") (pintype "passive"))
      (node (ref "DEC") (pin "AT2") (pinfunction "P$2_AT2") (pintype "bidirectional"))
      (node (ref "ECS") (pin "AT2") (pinfunction "P$2_AT2") (pintype "bidirectional"))
      (node (ref "EDAC") (pin "AT2") (pinfunction "P$2_AT2") (pintype "bidirectional"))
    )
    (net (code "90") (name "Net-(DECAG-P$2)") (class "Default")
      (node (ref "AX1") (pin "33") (pinfunction "33_33") (pintype "passive"))
      (node (ref "DEC") (pin "AU1") (pinfunction "P$2_AU1") (pintype "bidirectional"))
      (node (ref "ECS") (pin "AU1") (pinfunction "P$2_AU1") (pintype "bidirectional"))
      (node (ref "EDAC") (pin "AU1") (pinfunction "P$2_AU1") (pintype "bidirectional"))
    )
    (net (code "91") (name "Net-(DECAH-P$2)") (class "Default")
      (node (ref "AX2") (pin "33") (pinfunction "33_33") (pintype "passive"))
      (node (ref "DEC") (pin "AU2") (pinfunction "P$2_AU2") (pintype "bidirectional"))
      (node (ref "ECS") (pin "AU2") (pinfunction "P$2_AU2") (pintype "bidirectional"))
      (node (ref "EDAC") (pin "AU2") (pinfunction "P$2_AU2") (pintype "bidirectional"))
    )
    (net (code "92") (name "Net-(DECAI-P$2)") (class "Default")
      (node (ref "AX1") (pin "35") (pinfunction "35_35") (pintype "passive"))
      (node (ref "DEC") (pin "AV1") (pinfunction "P$2_AV1") (pintype "bidirectional"))
      (node (ref "ECS") (pin "AV1") (pinfunction "P$2_AV1") (pintype "bidirectional"))
      (node (ref "EDAC") (pin "AV1") (pinfunction "P$2_AV1") (pintype "bidirectional"))
    )
    (net (code "93") (name "Net-(DECAJ-P$2)") (class "Default")
      (node (ref "AX2") (pin "35") (pinfunction "35_35") (pintype "passive"))
      (node (ref "DEC") (pin "AV2") (pinfunction "P$2_AV2") (pintype "bidirectional"))
      (node (ref "ECS") (pin "AV2") (pinfunction "P$2_AV2") (pintype "bidirectional"))
      (node (ref "EDAC") (pin "AV2") (pinfunction "P$2_AV2") (pintype "bidirectional"))
    )
    (net (code "94") (name "Net-(DECAK-P$2)") (class "Default")
      (node (ref "BX1") (pin "1") (pinfunction "1_1") (pintype "passive"))
      (node (ref "DEC") (pin "BA1") (pinfunction "P$2_BA1") (pintype "bidirectional"))
      (node (ref "ECS") (pin "BA1") (pinfunction "P$2_BA1") (pintype "bidirectional"))
      (node (ref "EDAC") (pin "BA1") (pinfunction "P$2_BA1") (pintype "bidirectional"))
    )
    (net (code "95") (name "Net-(DECAL-P$2)") (class "Default")
      (node (ref "BX2") (pin "1") (pinfunction "1_1") (pintype "passive"))
      (node (ref "DEC") (pin "BA2") (pinfunction "P$2_BA2") (pintype "bidirectional"))
      (node (ref "ECS") (pin "BA2") (pinfunction "P$2_BA2") (pintype "bidirectional"))
      (node (ref "EDAC") (pin "BA2") (pinfunction "P$2_BA2") (pintype "bidirectional"))
    )
    (net (code "96") (name "Net-(DECAM-P$2)") (class "Default")
      (node (ref "BX1") (pin "3") (pinfunction "3_3") (pintype "passive"))
      (node (ref "DEC") (pin "BB1") (pinfunction "P$2_BB1") (pintype "bidirectional"))
      (node (ref "ECS") (pin "BB1") (pinfunction "P$2_BB1") (pintype "bidirectional"))
      (node (ref "EDAC") (pin "BB1") (pinfunction "P$2_BB1") (pintype "bidirectional"))
    )
    (net (code "97") (name "Net-(DECAN-P$2)") (class "Default")
      (node (ref "BX2") (pin "3") (pinfunction "3_3") (pintype "passive"))
      (node (ref "DEC") (pin "BB2") (pinfunction "P$2_BB2") (pintype "bidirectional"))
      (node (ref "ECS") (pin "BB2") (pinfunction "P$2_BB2") (pintype "bidirectional"))
      (node (ref "EDAC") (pin "BB2") (pinfunction "P$2_BB2") (pintype "bidirectional"))
    )
    (net (code "98") (name "Net-(DECAO-P$2)") (class "Default")
      (node (ref "BX1") (pin "5") (pinfunction "5_5") (pintype "passive"))
      (node (ref "DEC") (pin "BC1") (pinfunction "P$2_BC1") (pintype "bidirectional"))
      (node (ref "ECS") (pin "BC1") (pinfunction "P$2_BC1") (pintype "bidirectional"))
      (node (ref "EDAC") (pin "BC1") (pinfunction "P$2_BC1") (pintype "bidirectional"))
    )
    (net (code "99") (name "Net-(DECAP-P$2)") (class "Default")
      (node (ref "BX2") (pin "5") (pinfunction "5_5") (pintype "passive"))
      (node (ref "DEC") (pin "BC2") (pinfunction "P$2_BC2") (pintype "bidirectional"))
      (node (ref "ECS") (pin "BC2") (pinfunction "P$2_BC2") (pintype "bidirectional"))
      (node (ref "EDAC") (pin "BC2") (pinfunction "P$2_BC2") (pintype "bidirectional"))
    )
    (net (code "100") (name "Net-(DECAQ-P$2)") (class "Default")
      (node (ref "BX1") (pin "7") (pinfunction "7_7") (pintype "passive"))
      (node (ref "DEC") (pin "BD1") (pinfunction "P$2_BD1") (pintype "bidirectional"))
      (node (ref "ECS") (pin "BD1") (pinfunction "P$2_BD1") (pintype "bidirectional"))
      (node (ref "EDAC") (pin "BD1") (pinfunction "P$2_BD1") (pintype "bidirectional"))
    )
    (net (code "101") (name "Net-(DECAR-P$2)") (class "Default")
      (node (ref "BX2") (pin "7") (pinfunction "7_7") (pintype "passive"))
      (node (ref "DEC") (pin "BD2") (pinfunction "P$2_BD2") (pintype "bidirectional"))
      (node (ref "ECS") (pin "BD2") (pinfunction "P$2_BD2") (pintype "bidirectional"))
      (node (ref "EDAC") (pin "BD2") (pinfunction "P$2_BD2") (pintype "bidirectional"))
    )
    (net (code "102") (name "Net-(DECAS-P$2)") (class "Default")
      (node (ref "BX1") (pin "9") (pinfunction "9_9") (pintype "passive"))
      (node (ref "DEC") (pin "BE1") (pinfunction "P$2_BE1") (pintype "bidirectional"))
      (node (ref "ECS") (pin "BE1") (pinfunction "P$2_BE1") (pintype "bidirectional"))
      (node (ref "EDAC") (pin "BE1") (pinfunction "P$2_BE1") (pintype "bidirectional"))
    )
    (net (code "103") (name "Net-(DECAT-P$2)") (class "Default")
      (node (ref "BX2") (pin "9") (pinfunction "9_9") (pintype "passive"))
      (node (ref "DEC") (pin "BE2") (pinfunction "P$2_BE2") (pintype "bidirectional"))
      (node (ref "ECS") (pin "BE2") (pinfunction "P$2_BE2") (pintype "bidirectional"))
      (node (ref "EDAC") (pin "BE2") (pinfunction "P$2_BE2") (pintype "bidirectional"))
    )
    (net (code "104") (name "Net-(DECAU-P$2)") (class "Default")
      (node (ref "BX1") (pin "11") (pinfunction "11_11") (pintype "passive"))
      (node (ref "DEC") (pin "BF1") (pinfunction "P$2_BF1") (pintype "bidirectional"))
      (node (ref "ECS") (pin "BF1") (pinfunction "P$2_BF1") (pintype "bidirectional"))
      (node (ref "EDAC") (pin "BF1") (pinfunction "P$2_BF1") (pintype "bidirectional"))
    )
    (net (code "105") (name "Net-(DECAV-P$2)") (class "Default")
      (node (ref "BX2") (pin "11") (pinfunction "11_11") (pintype "passive"))
      (node (ref "DEC") (pin "BF2") (pinfunction "P$2_BF2") (pintype "bidirectional"))
      (node (ref "ECS") (pin "BF2") (pinfunction "P$2_BF2") (pintype "bidirectional"))
      (node (ref "EDAC") (pin "BF2") (pinfunction "P$2_BF2") (pintype "bidirectional"))
    )
    (net (code "106") (name "Net-(DECAW-P$2)") (class "Default")
      (node (ref "BX1") (pin "13") (pinfunction "13_13") (pintype "passive"))
      (node (ref "DEC") (pin "BH1") (pinfunction "P$2_BH1") (pintype "bidirectional"))
      (node (ref "ECS") (pin "BH1") (pinfunction "P$2_BH1") (pintype "bidirectional"))
      (node (ref "EDAC") (pin "BH1") (pinfunction "P$2_BH1") (pintype "bidirectional"))
    )
    (net (code "107") (name "Net-(DECAX-P$2)") (class "Default")
      (node (ref "BX2") (pin "13") (pinfunction "13_13") (pintype "passive"))
      (node (ref "DEC") (pin "BH2") (pinfunction "P$2_BH2") (pintype "bidirectional"))
      (node (ref "ECS") (pin "BH2") (pinfunction "P$2_BH2") (pintype "bidirectional"))
      (node (ref "EDAC") (pin "BH2") (pinfunction "P$2_BH2") (pintype "bidirectional"))
    )
    (net (code "108") (name "Net-(DECAY-P$2)") (class "Default")
      (node (ref "BX1") (pin "15") (pinfunction "15_15") (pintype "passive"))
      (node (ref "DEC") (pin "BJ1") (pinfunction "P$2_BJ1") (pintype "bidirectional"))
      (node (ref "ECS") (pin "BJ1") (pinfunction "P$2_BJ1") (pintype "bidirectional"))
      (node (ref "EDAC") (pin "BJ1") (pinfunction "P$2_BJ1") (pintype "bidirectional"))
    )
    (net (code "109") (name "Net-(DECAZ-P$2)") (class "Default")
      (node (ref "BX2") (pin "15") (pinfunction "15_15") (pintype "passive"))
      (node (ref "DEC") (pin "BJ2") (pinfunction "P$2_BJ2") (pintype "bidirectional"))
      (node (ref "ECS") (pin "BJ2") (pinfunction "P$2_BJ2") (pintype "bidirectional"))
      (node (ref "EDAC") (pin "BJ2") (pinfunction "P$2_BJ2") (pintype "bidirectional"))
    )
    (net (code "110") (name "Net-(DECB-P$2)") (class "Default")
      (node (ref "AX2") (pin "1") (pinfunction "1_1") (pintype "passive"))
      (node (ref "DEC") (pin "AA2") (pinfunction "P$2_AA2") (pintype "bidirectional"))
      (node (ref "ECS") (pin "AA2") (pinfunction "P$2_AA2") (pintype "bidirectional"))
      (node (ref "EDAC") (pin "AA2") (pinfunction "P$2_AA2") (pintype "bidirectional"))
    )
    (net (code "111") (name "Net-(DECBA-P$2)") (class "Default")
      (node (ref "BX1") (pin "17") (pinfunction "17_17") (pintype "passive"))
      (node (ref "DEC") (pin "BK1") (pinfunction "P$2_BK1") (pintype "bidirectional"))
      (node (ref "ECS") (pin "BK1") (pinfunction "P$2_BK1") (pintype "bidirectional"))
      (node (ref "EDAC") (pin "BK1") (pinfunction "P$2_BK1") (pintype "bidirectional"))
    )
    (net (code "112") (name "Net-(DECBB-P$2)") (class "Default")
      (node (ref "BX2") (pin "17") (pinfunction "17_17") (pintype "passive"))
      (node (ref "DEC") (pin "BK2") (pinfunction "P$2_BK2") (pintype "bidirectional"))
      (node (ref "ECS") (pin "BK2") (pinfunction "P$2_BK2") (pintype "bidirectional"))
      (node (ref "EDAC") (pin "BK2") (pinfunction "P$2_BK2") (pintype "bidirectional"))
    )
    (net (code "113") (name "Net-(DECBC-P$2)") (class "Default")
      (node (ref "BX1") (pin "19") (pinfunction "19_19") (pintype "passive"))
      (node (ref "DEC") (pin "BL1") (pinfunction "P$2_BL1") (pintype "bidirectional"))
      (node (ref "ECS") (pin "BL1") (pinfunction "P$2_BL1") (pintype "bidirectional"))
      (node (ref "EDAC") (pin "BL1") (pinfunction "P$2_BL1") (pintype "bidirectional"))
    )
    (net (code "114") (name "Net-(DECBD-P$2)") (class "Default")
      (node (ref "BX2") (pin "19") (pinfunction "19_19") (pintype "passive"))
      (node (ref "DEC") (pin "BL2") (pinfunction "P$2_BL2") (pintype "bidirectional"))
      (node (ref "ECS") (pin "BL2") (pinfunction "P$2_BL2") (pintype "bidirectional"))
      (node (ref "EDAC") (pin "BL2") (pinfunction "P$2_BL2") (pintype "bidirectional"))
    )
    (net (code "115") (name "Net-(DECBE-P$2)") (class "Default")
      (node (ref "BX1") (pin "21") (pinfunction "21_21") (pintype "passive"))
      (node (ref "DEC") (pin "BM1") (pinfunction "P$2_BM1") (pintype "bidirectional"))
      (node (ref "ECS") (pin "BM1") (pinfunction "P$2_BM1") (pintype "bidirectional"))
      (node (ref "EDAC") (pin "BM1") (pinfunction "P$2_BM1") (pintype "bidirectional"))
    )
    (net (code "116") (name "Net-(DECBF-P$2)") (class "Default")
      (node (ref "BX2") (pin "21") (pinfunction "21_21") (pintype "passive"))
      (node (ref "DEC") (pin "BM2") (pinfunction "P$2_BM2") (pintype "bidirectional"))
      (node (ref "ECS") (pin "BM2") (pinfunction "P$2_BM2") (pintype "bidirectional"))
      (node (ref "EDAC") (pin "BM2") (pinfunction "P$2_BM2") (pintype "bidirectional"))
    )
    (net (code "117") (name "Net-(DECBG-P$2)") (class "Default")
      (node (ref "BX1") (pin "23") (pinfunction "23_23") (pintype "passive"))
      (node (ref "DEC") (pin "BN1") (pinfunction "P$2_BN1") (pintype "bidirectional"))
      (node (ref "ECS") (pin "BN1") (pinfunction "P$2_BN1") (pintype "bidirectional"))
      (node (ref "EDAC") (pin "BN1") (pinfunction "P$2_BN1") (pintype "bidirectional"))
    )
    (net (code "118") (name "Net-(DECBH-P$2)") (class "Default")
      (node (ref "BX2") (pin "23") (pinfunction "23_23") (pintype "passive"))
      (node (ref "DEC") (pin "BN2") (pinfunction "P$2_BN2") (pintype "bidirectional"))
      (node (ref "ECS") (pin "BN2") (pinfunction "P$2_BN2") (pintype "bidirectional"))
      (node (ref "EDAC") (pin "BN2") (pinfunction "P$2_BN2") (pintype "bidirectional"))
    )
    (net (code "119") (name "Net-(DECBI-P$2)") (class "Default")
      (node (ref "BX1") (pin "25") (pinfunction "25_25") (pintype "passive"))
      (node (ref "DEC") (pin "BP1") (pinfunction "P$2_BP1") (pintype "bidirectional"))
      (node (ref "ECS") (pin "BP1") (pinfunction "P$2_BP1") (pintype "bidirectional"))
      (node (ref "EDAC") (pin "BP1") (pinfunction "P$2_BP1") (pintype "bidirectional"))
    )
    (net (code "120") (name "Net-(DECBJ-P$2)") (class "Default")
      (node (ref "BX2") (pin "25") (pinfunction "25_25") (pintype "passive"))
      (node (ref "DEC") (pin "BP2") (pinfunction "P$2_BP2") (pintype "bidirectional"))
      (node (ref "ECS") (pin "BP2") (pinfunction "P$2_BP2") (pintype "bidirectional"))
      (node (ref "EDAC") (pin "BP2") (pinfunction "P$2_BP2") (pintype "bidirectional"))
    )
    (net (code "121") (name "Net-(DECBK-P$2)") (class "Default")
      (node (ref "BX1") (pin "27") (pinfunction "27_27") (pintype "passive"))
      (node (ref "DEC") (pin "BR1") (pinfunction "P$2_BR1") (pintype "bidirectional"))
      (node (ref "ECS") (pin "BR1") (pinfunction "P$2_BR1") (pintype "bidirectional"))
      (node (ref "EDAC") (pin "BR1") (pinfunction "P$2_BR1") (pintype "bidirectional"))
    )
    (net (code "122") (name "Net-(DECBL-P$2)") (class "Default")
      (node (ref "BX2") (pin "27") (pinfunction "27_27") (pintype "passive"))
      (node (ref "DEC") (pin "BR2") (pinfunction "P$2_BR2") (pintype "bidirectional"))
      (node (ref "ECS") (pin "BR2") (pinfunction "P$2_BR2") (pintype "bidirectional"))
      (node (ref "EDAC") (pin "BR2") (pinfunction "P$2_BR2") (pintype "bidirectional"))
    )
    (net (code "123") (name "Net-(DECBM-P$2)") (class "Default")
      (node (ref "BX1") (pin "29") (pinfunction "29_29") (pintype "passive"))
      (node (ref "DEC") (pin "BS1") (pinfunction "P$2_BS1") (pintype "bidirectional"))
      (node (ref "ECS") (pin "BS1") (pinfunction "P$2_BS1") (pintype "bidirectional"))
      (node (ref "EDAC") (pin "BS1") (pinfunction "P$2_BS1") (pintype "bidirectional"))
    )
    (net (code "124") (name "Net-(DECBN-P$2)") (class "Default")
      (node (ref "BX2") (pin "29") (pinfunction "29_29") (pintype "passive"))
      (node (ref "DEC") (pin "BS2") (pinfunction "P$2_BS2") (pintype "bidirectional"))
      (node (ref "ECS") (pin "BS2") (pinfunction "P$2_BS2") (pintype "bidirectional"))
      (node (ref "EDAC") (pin "BS2") (pinfunction "P$2_BS2") (pintype "bidirectional"))
    )
    (net (code "125") (name "Net-(DECBO-P$2)") (class "Default")
      (node (ref "BX1") (pin "31") (pinfunction "31_31") (pintype "passive"))
      (node (ref "DEC") (pin "BT1") (pinfunction "P$2_BT1") (pintype "bidirectional"))
      (node (ref "ECS") (pin "BT1") (pinfunction "P$2_BT1") (pintype "bidirectional"))
      (node (ref "EDAC") (pin "BT1") (pinfunction "P$2_BT1") (pintype "bidirectional"))
    )
    (net (code "126") (name "Net-(DECBP-P$2)") (class "Default")
      (node (ref "BX2") (pin "31") (pinfunction "31_31") (pintype "passive"))
      (node (ref "DEC") (pin "BT2") (pinfunction "P$2_BT2") (pintype "bidirectional"))
      (node (ref "ECS") (pin "BT2") (pinfunction "P$2_BT2") (pintype "bidirectional"))
      (node (ref "EDAC") (pin "BT2") (pinfunction "P$2_BT2") (pintype "bidirectional"))
    )
    (net (code "127") (name "Net-(DECBQ-P$2)") (class "Default")
      (node (ref "BX1") (pin "33") (pinfunction "33_33") (pintype "passive"))
      (node (ref "DEC") (pin "BU1") (pinfunction "P$2_BU1") (pintype "bidirectional"))
      (node (ref "ECS") (pin "BU1") (pinfunction "P$2_BU1") (pintype "bidirectional"))
      (node (ref "EDAC") (pin "BU1") (pinfunction "P$2_BU1") (pintype "bidirectional"))
    )
    (net (code "128") (name "Net-(DECBR-P$2)") (class "Default")
      (node (ref "BX2") (pin "33") (pinfunction "33_33") (pintype "passive"))
      (node (ref "DEC") (pin "BU2") (pinfunction "P$2_BU2") (pintype "bidirectional"))
      (node (ref "ECS") (pin "BU2") (pinfunction "P$2_BU2") (pintype "bidirectional"))
      (node (ref "EDAC") (pin "BU2") (pinfunction "P$2_BU2") (pintype "bidirectional"))
    )
    (net (code "129") (name "Net-(DECBS-P$2)") (class "Default")
      (node (ref "BX1") (pin "35") (pinfunction "35_35") (pintype "passive"))
      (node (ref "DEC") (pin "BV1") (pinfunction "P$2_BV1") (pintype "bidirectional"))
      (node (ref "ECS") (pin "BV1") (pinfunction "P$2_BV1") (pintype "bidirectional"))
      (node (ref "EDAC") (pin "BV1") (pinfunction "P$2_BV1") (pintype "bidirectional"))
    )
    (net (code "130") (name "Net-(DECBT-P$2)") (class "Default")
      (node (ref "BX2") (pin "35") (pinfunction "35_35") (pintype "passive"))
      (node (ref "DEC") (pin "BV2") (pinfunction "P$2_BV2") (pintype "bidirectional"))
      (node (ref "ECS") (pin "BV2") (pinfunction "P$2_BV2") (pintype "bidirectional"))
      (node (ref "EDAC") (pin "BV2") (pinfunction "P$2_BV2") (pintype "bidirectional"))
    )
    (net (code "131") (name "Net-(DECC-P$2)") (class "Default")
      (node (ref "AX1") (pin "3") (pinfunction "3_3") (pintype "passive"))
      (node (ref "DEC") (pin "AB1") (pinfunction "P$2_AB1") (pintype "bidirectional"))
      (node (ref "ECS") (pin "AB1") (pinfunction "P$2_AB1") (pintype "bidirectional"))
      (node (ref "EDAC") (pin "AB1") (pinfunction "P$2_AB1") (pintype "bidirectional"))
    )
    (net (code "132") (name "Net-(DECD-P$2)") (class "Default")
      (node (ref "AX2") (pin "3") (pinfunction "3_3") (pintype "passive"))
      (node (ref "DEC") (pin "AB2") (pinfunction "P$2_AB2") (pintype "bidirectional"))
      (node (ref "ECS") (pin "AB2") (pinfunction "P$2_AB2") (pintype "bidirectional"))
      (node (ref "EDAC") (pin "AB2") (pinfunction "P$2_AB2") (pintype "bidirectional"))
    )
    (net (code "133") (name "Net-(DECE-P$2)") (class "Default")
      (node (ref "AX1") (pin "5") (pinfunction "5_5") (pintype "passive"))
      (node (ref "DEC") (pin "AC1") (pinfunction "P$2_AC1") (pintype "bidirectional"))
      (node (ref "ECS") (pin "AC1") (pinfunction "P$2_AC1") (pintype "bidirectional"))
      (node (ref "EDAC") (pin "AC1") (pinfunction "P$2_AC1") (pintype "bidirectional"))
    )
    (net (code "134") (name "Net-(DECF-P$2)") (class "Default")
      (node (ref "AX2") (pin "5") (pinfunction "5_5") (pintype "passive"))
      (node (ref "DEC") (pin "AC2") (pinfunction "P$2_AC2") (pintype "bidirectional"))
      (node (ref "ECS") (pin "AC2") (pinfunction "P$2_AC2") (pintype "bidirectional"))
      (node (ref "EDAC") (pin "AC2") (pinfunction "P$2_AC2") (pintype "bidirectional"))
    )
    (net (code "135") (name "Net-(DECG-P$2)") (class "Default")
      (node (ref "AX1") (pin "7") (pinfunction "7_7") (pintype "passive"))
      (node (ref "DEC") (pin "AD1") (pinfunction "P$2_AD1") (pintype "bidirectional"))
      (node (ref "ECS") (pin "AD1") (pinfunction "P$2_AD1") (pintype "bidirectional"))
      (node (ref "EDAC") (pin "AD1") (pinfunction "P$2_AD1") (pintype "bidirectional"))
    )
    (net (code "136") (name "Net-(DECH-P$2)") (class "Default")
      (node (ref "AX2") (pin "7") (pinfunction "7_7") (pintype "passive"))
      (node (ref "DEC") (pin "AD2") (pinfunction "P$2_AD2") (pintype "bidirectional"))
      (node (ref "ECS") (pin "AD2") (pinfunction "P$2_AD2") (pintype "bidirectional"))
      (node (ref "EDAC") (pin "AD2") (pinfunction "P$2_AD2") (pintype "bidirectional"))
    )
    (net (code "137") (name "Net-(DECI-P$2)") (class "Default")
      (node (ref "AX1") (pin "9") (pinfunction "9_9") (pintype "passive"))
      (node (ref "DEC") (pin "AE1") (pinfunction "P$2_AE1") (pintype "bidirectional"))
      (node (ref "ECS") (pin "AE1") (pinfunction "P$2_AE1") (pintype "bidirectional"))
      (node (ref "EDAC") (pin "AE1") (pinfunction "P$2_AE1") (pintype "bidirectional"))
    )
    (net (code "138") (name "Net-(DECJ-P$2)") (class "Default")
      (node (ref "AX2") (pin "9") (pinfunction "9_9") (pintype "passive"))
      (node (ref "DEC") (pin "AE2") (pinfunction "P$2_AE2") (pintype "bidirectional"))
      (node (ref "ECS") (pin "AE2") (pinfunction "P$2_AE2") (pintype "bidirectional"))
      (node (ref "EDAC") (pin "AE2") (pinfunction "P$2_AE2") (pintype "bidirectional"))
    )
    (net (code "139") (name "Net-(DECK-P$2)") (class "Default")
      (node (ref "AX1") (pin "11") (pinfunction "11_11") (pintype "passive"))
      (node (ref "DEC") (pin "AF1") (pinfunction "P$2_AF1") (pintype "bidirectional"))
      (node (ref "ECS") (pin "AF1") (pinfunction "P$2_AF1") (pintype "bidirectional"))
      (node (ref "EDAC") (pin "AF1") (pinfunction "P$2_AF1") (pintype "bidirectional"))
    )
    (net (code "140") (name "Net-(DECL-P$2)") (class "Default")
      (node (ref "AX2") (pin "11") (pinfunction "11_11") (pintype "passive"))
      (node (ref "DEC") (pin "AF2") (pinfunction "P$2_AF2") (pintype "bidirectional"))
      (node (ref "ECS") (pin "AF2") (pinfunction "P$2_AF2") (pintype "bidirectional"))
      (node (ref "EDAC") (pin "AF2") (pinfunction "P$2_AF2") (pintype "bidirectional"))
    )
    (net (code "141") (name "Net-(DECM-P$2)") (class "Default")
      (node (ref "AX1") (pin "13") (pinfunction "13_13") (pintype "passive"))
      (node (ref "DEC") (pin "AH1") (pinfunction "P$2_AH1") (pintype "bidirectional"))
      (node (ref "ECS") (pin "AH1") (pinfunction "P$2_AH1") (pintype "bidirectional"))
      (node (ref "EDAC") (pin "AH1") (pinfunction "P$2_AH1") (pintype "bidirectional"))
    )
    (net (code "142") (name "Net-(DECN-P$2)") (class "Default")
      (node (ref "AX2") (pin "13") (pinfunction "13_13") (pintype "passive"))
      (node (ref "DEC") (pin "AH2") (pinfunction "P$2_AH2") (pintype "bidirectional"))
      (node (ref "ECS") (pin "AH2") (pinfunction "P$2_AH2") (pintype "bidirectional"))
      (node (ref "EDAC") (pin "AH2") (pinfunction "P$2_AH2") (pintype "bidirectional"))
    )
    (net (code "143") (name "Net-(DECO-P$2)") (class "Default")
      (node (ref "AX1") (pin "15") (pinfunction "15_15") (pintype "passive"))
      (node (ref "DEC") (pin "AJ1") (pinfunction "P$2_AJ1") (pintype "bidirectional"))
      (node (ref "ECS") (pin "AJ1") (pinfunction "P$2_AJ1") (pintype "bidirectional"))
      (node (ref "EDAC") (pin "AJ1") (pinfunction "P$2_AJ1") (pintype "bidirectional"))
    )
    (net (code "144") (name "Net-(DECP-P$2)") (class "Default")
      (node (ref "AX2") (pin "15") (pinfunction "15_15") (pintype "passive"))
      (node (ref "DEC") (pin "AJ2") (pinfunction "P$2_AJ2") (pintype "bidirectional"))
      (node (ref "ECS") (pin "AJ2") (pinfunction "P$2_AJ2") (pintype "bidirectional"))
      (node (ref "EDAC") (pin "AJ2") (pinfunction "P$2_AJ2") (pintype "bidirectional"))
    )
    (net (code "145") (name "Net-(DECQ-P$2)") (class "Default")
      (node (ref "AX1") (pin "17") (pinfunction "17_17") (pintype "passive"))
      (node (ref "DEC") (pin "AK1") (pinfunction "P$2_AK1") (pintype "bidirectional"))
      (node (ref "ECS") (pin "AK1") (pinfunction "P$2_AK1") (pintype "bidirectional"))
      (node (ref "EDAC") (pin "AK1") (pinfunction "P$2_AK1") (pintype "bidirectional"))
    )
    (net (code "146") (name "Net-(DECR-P$2)") (class "Default")
      (node (ref "AX2") (pin "17") (pinfunction "17_17") (pintype "passive"))
      (node (ref "DEC") (pin "AK2") (pinfunction "P$2_AK2") (pintype "bidirectional"))
      (node (ref "ECS") (pin "AK2") (pinfunction "P$2_AK2") (pintype "bidirectional"))
      (node (ref "EDAC") (pin "AK2") (pinfunction "P$2_AK2") (pintype "bidirectional"))
    )
    (net (code "147") (name "Net-(DECS-P$2)") (class "Default")
      (node (ref "AX1") (pin "19") (pinfunction "19_19") (pintype "passive"))
      (node (ref "DEC") (pin "AL1") (pinfunction "P$2_AL1") (pintype "bidirectional"))
      (node (ref "ECS") (pin "AL1") (pinfunction "P$2_AL1") (pintype "bidirectional"))
      (node (ref "EDAC") (pin "AL1") (pinfunction "P$2_AL1") (pintype "bidirectional"))
    )
    (net (code "148") (name "Net-(DECT-P$2)") (class "Default")
      (node (ref "AX2") (pin "19") (pinfunction "19_19") (pintype "passive"))
      (node (ref "DEC") (pin "AL2") (pinfunction "P$2_AL2") (pintype "bidirectional"))
      (node (ref "ECS") (pin "AL2") (pinfunction "P$2_AL2") (pintype "bidirectional"))
      (node (ref "EDAC") (pin "AL2") (pinfunction "P$2_AL2") (pintype "bidirectional"))
    )
    (net (code "149") (name "Net-(DECU-P$2)") (class "Default")
      (node (ref "AX1") (pin "21") (pinfunction "21_21") (pintype "passive"))
      (node (ref "DEC") (pin "AM1") (pinfunction "P$2_AM1") (pintype "bidirectional"))
      (node (ref "ECS") (pin "AM1") (pinfunction "P$2_AM1") (pintype "bidirectional"))
      (node (ref "EDAC") (pin "AM1") (pinfunction "P$2_AM1") (pintype "bidirectional"))
    )
    (net (code "150") (name "Net-(DECV-P$2)") (class "Default")
      (node (ref "AX2") (pin "21") (pinfunction "21_21") (pintype "passive"))
      (node (ref "DEC") (pin "AM2") (pinfunction "P$2_AM2") (pintype "bidirectional"))
      (node (ref "ECS") (pin "AM2") (pinfunction "P$2_AM2") (pintype "bidirectional"))
      (node (ref "EDAC") (pin "AM2") (pinfunction "P$2_AM2") (pintype "bidirectional"))
    )
    (net (code "151") (name "Net-(DECW-P$2)") (class "Default")
      (node (ref "AX1") (pin "23") (pinfunction "23_23") (pintype "passive"))
      (node (ref "DEC") (pin "AN1") (pinfunction "P$2_AN1") (pintype "bidirectional"))
      (node (ref "ECS") (pin "AN1") (pinfunction "P$2_AN1") (pintype "bidirectional"))
      (node (ref "EDAC") (pin "AN1") (pinfunction "P$2_AN1") (pintype "bidirectional"))
    )
    (net (code "152") (name "Net-(DECX-P$2)") (class "Default")
      (node (ref "AX2") (pin "23") (pinfunction "23_23") (pintype "passive"))
      (node (ref "DEC") (pin "AN2") (pinfunction "P$2_AN2") (pintype "bidirectional"))
      (node (ref "ECS") (pin "AN2") (pinfunction "P$2_AN2") (pintype "bidirectional"))
      (node (ref "EDAC") (pin "AN2") (pinfunction "P$2_AN2") (pintype "bidirectional"))
    )
    (net (code "153") (name "Net-(DECY-P$2)") (class "Default")
      (node (ref "AX1") (pin "25") (pinfunction "25_25") (pintype "passive"))
      (node (ref "DEC") (pin "AP1") (pinfunction "P$2_AP1") (pintype "bidirectional"))
      (node (ref "ECS") (pin "AP1") (pinfunction "P$2_AP1") (pintype "bidirectional"))
      (node (ref "EDAC") (pin "AP1") (pinfunction "P$2_AP1") (pintype "bidirectional"))
    )
    (net (code "154") (name "Net-(DECZ-P$2)") (class "Default")
      (node (ref "AX2") (pin "25") (pinfunction "25_25") (pintype "passive"))
      (node (ref "DEC") (pin "AP2") (pinfunction "P$2_AP2") (pintype "bidirectional"))
      (node (ref "ECS") (pin "AP2") (pinfunction "P$2_AP2") (pintype "bidirectional"))
      (node (ref "EDAC") (pin "AP2") (pinfunction "P$2_AP2") (pintype "bidirectional"))
    )
    (net (code "155") (name "Net-(GREEN-C)") (class "Default")
      (node (ref "GREEN") (pin "K") (pinfunction "C_K") (pintype "passive"))
      (node (ref "R2") (pin "2") (pinfunction "2_2") (pintype "passive"))
    )
    (net (code "156") (name "Net-(LOADHI1-Pad1)") (class "Default")
      (node (ref "LOADHI1") (pin "1") (pinfunction "1_1") (pintype "passive"))
      (node (ref "R11") (pin "2") (pinfunction "2_2") (pintype "passive"))
    )
    (net (code "157") (name "Net-(LOADHI3-Pad1)") (class "Default")
      (node (ref "LOADHI3") (pin "1") (pinfunction "1_1") (pintype "passive"))
      (node (ref "R10") (pin "2") (pinfunction "2_2") (pintype "passive"))
    )
    (net (code "158") (name "Net-(LOADL1-Pad1)") (class "Default")
      (node (ref "LOADL1") (pin "1") (pinfunction "1_1") (pintype "passive"))
      (node (ref "R8") (pin "1") (pinfunction "1_1") (pintype "passive"))
      (node (ref "R9") (pin "1") (pinfunction "1_1") (pintype "passive"))
    )
    (net (code "159") (name "Net-(LOADL3-Pad1)") (class "Default")
      (node (ref "LOADL3") (pin "1") (pinfunction "1_1") (pintype "passive"))
      (node (ref "R6") (pin "1") (pinfunction "1_1") (pintype "passive"))
      (node (ref "R7") (pin "1") (pinfunction "1_1") (pintype "passive"))
    )
    (net (code "160") (name "Net-(PWR-C)") (class "Default")
      (node (ref "PWR") (pin "K") (pinfunction "C_K") (pintype "passive"))
      (node (ref "R14") (pin "2") (pinfunction "2_2") (pintype "passive"))
    )
    (net (code "161") (name "Net-(RED1-C)") (class "Default")
      (node (ref "R3") (pin "2") (pinfunction "2_2") (pintype "passive"))
      (node (ref "RED1") (pin "K") (pinfunction "C_K") (pintype "passive"))
    )
    (net (code "162") (name "Net-(RED2-C)") (class "Default")
      (node (ref "R5") (pin "2") (pinfunction "2_2") (pintype "passive"))
      (node (ref "RED2") (pin "K") (pinfunction "C_K") (pintype "passive"))
    )
    (net (code "163") (name "Net-(UUT_PWR-C)") (class "Default")
      (node (ref "R12") (pin "2") (pinfunction "2_2") (pintype "passive"))
      (node (ref "R13") (pin "2") (pinfunction "2_2") (pintype "passive"))
      (node (ref "UUT_PWR") (pin "K") (pinfunction "C_K") (pintype "passive"))
    )
    (net (code "164") (name "Net-(YELLOW-C)") (class "Default")
      (node (ref "R4") (pin "2") (pinfunction "2_2") (pintype "passive"))
      (node (ref "YELLOW") (pin "K") (pinfunction "C_K") (pintype "passive"))
    )
    (net (code "165") (name "VCC") (class "Default")
      (node (ref "D1") (pin "A") (pinfunction "A_A") (pintype "passive"))
      (node (ref "IC6") (pin "14") (pinfunction "14_14") (pintype "passive"))
      (node (ref "POWER") (pin "3") (pinfunction "3_3") (pintype "passive"))
      (node (ref "R6") (pin "2") (pinfunction "2_2") (pintype "passive"))
      (node (ref "R7") (pin "2") (pinfunction "2_2") (pintype "passive"))
      (node (ref "R8") (pin "2") (pinfunction "2_2") (pintype "passive"))
      (node (ref "R9") (pin "2") (pinfunction "2_2") (pintype "passive"))
      (node (ref "UUT") (pin "2") (pinfunction "P_2") (pintype "passive"))
    )
    (net (code "166") (name "VDD") (class "Default")
      (node (ref "C2") (pin "1") (pinfunction "1_1") (pintype "passive"))
      (node (ref "C3") (pin "1") (pinfunction "1_1") (pintype "passive"))
      (node (ref "C4") (pin "1") (pinfunction "1_1") (pintype "passive"))
      (node (ref "C5") (pin "1") (pinfunction "1_1") (pintype "passive"))
      (node (ref "C6") (pin "1") (pinfunction "1_1") (pintype "passive"))
      (node (ref "C7") (pin "1") (pinfunction "1_1") (pintype "passive"))
      (node (ref "D2") (pin "C") (pinfunction "C_C") (pintype "passive"))
      (node (ref "IC1") (pin "9") (pinfunction "VDD_9") (pintype "power_in"))
      (node (ref "IC2") (pin "9") (pinfunction "VDD_9") (pintype "power_in"))
      (node (ref "IC3") (pin "9") (pinfunction "VDD_9") (pintype "power_in"))
      (node (ref "IC4") (pin "9") (pinfunction "VDD_9") (pintype "power_in"))
      (node (ref "IC5") (pin "9") (pinfunction "VDD_9") (pintype "power_in"))
      (node (ref "PWR") (pin "A") (pinfunction "A_A") (pintype "passive"))
    )
    (net (code "167") (name "VPP") (class "Default")
      (node (ref "AX2") (pin "2") (pinfunction "2_2") (pintype "passive"))
      (node (ref "BX2") (pin "2") (pinfunction "2_2") (pintype "passive"))
      (node (ref "C1") (pin "+") (pinfunction "+_+") (pintype "passive"))
      (node (ref "IC3") (pin "23") (pinfunction "GPA2_23") (pintype "bidirectional"))
      (node (ref "R1") (pin "2") (pinfunction "2_2") (pintype "passive"))
      (node (ref "UUT") (pin "3") (pinfunction "S_3") (pintype "passive"))
      (node (ref "UUT_PWR") (pin "A") (pinfunction "A_A") (pintype "passive"))
      (node (ref "VPP") (pin "1") (pinfunction "1_1") (pintype "passive"))
    )
    (net (code "168") (name "unconnected-(IC1-INTA-Pad20)") (class "Default")
      (node (ref "IC1") (pin "20") (pinfunction "INTA_20") (pintype "output"))
    )
    (net (code "169") (name "unconnected-(IC1-INTB-Pad19)") (class "Default")
      (node (ref "IC1") (pin "19") (pinfunction "INTB_19") (pintype "output"))
    )
    (net (code "170") (name "unconnected-(IC2-INTA-Pad20)") (class "Default")
      (node (ref "IC2") (pin "20") (pinfunction "INTA_20") (pintype "output"))
    )
    (net (code "171") (name "unconnected-(IC2-INTB-Pad19)") (class "Default")
      (node (ref "IC2") (pin "19") (pinfunction "INTB_19") (pintype "output"))
    )
    (net (code "172") (name "unconnected-(IC3-INTA-Pad20)") (class "Default")
      (node (ref "IC3") (pin "20") (pinfunction "INTA_20") (pintype "output"))
    )
    (net (code "173") (name "unconnected-(IC3-INTB-Pad19)") (class "Default")
      (node (ref "IC3") (pin "19") (pinfunction "INTB_19") (pintype "output"))
    )
    (net (code "174") (name "unconnected-(IC4-INTA-Pad20)") (class "Default")
      (node (ref "IC4") (pin "20") (pinfunction "INTA_20") (pintype "output"))
    )
    (net (code "175") (name "unconnected-(IC4-INTB-Pad19)") (class "Default")
      (node (ref "IC4") (pin "19") (pinfunction "INTB_19") (pintype "output"))
    )
    (net (code "176") (name "unconnected-(IC5-INTA-Pad20)") (class "Default")
      (node (ref "IC5") (pin "20") (pinfunction "INTA_20") (pintype "output"))
    )
    (net (code "177") (name "unconnected-(IC5-INTB-Pad19)") (class "Default")
      (node (ref "IC5") (pin "19") (pinfunction "INTB_19") (pintype "output"))
    )
    (net (code "178") (name "unconnected-(PC1-Pad1)") (class "Default")
      (node (ref "PC1") (pin "1") (pinfunction "1_1") (pintype "passive"))
    )
    (net (code "179") (name "unconnected-(PC1-Pad2)") (class "Default")
      (node (ref "PC1") (pin "2") (pinfunction "2_2") (pintype "passive"))
    )
    (net (code "180") (name "unconnected-(PC1-Pad5)") (class "Default")
      (node (ref "PC1") (pin "5") (pinfunction "5_5") (pintype "passive"))
    )
    (net (code "181") (name "unconnected-(PC1-Pad7)") (class "Default")
      (node (ref "PC1") (pin "7") (pinfunction "7_7") (pintype "passive"))
    )
    (net (code "182") (name "unconnected-(POWER-Pad4)") (class "Default")
      (node (ref "POWER") (pin "4") (pinfunction "4_4") (pintype "passive"))
    )
    (net (code "183") (name "unconnected-(POWER-Pad5)") (class "Default")
      (node (ref "POWER") (pin "5") (pinfunction "5_5") (pintype "passive"))
    )
    (net (code "184") (name "unconnected-(POWER-Pad6)") (class "Default")
      (node (ref "POWER") (pin "6") (pinfunction "6_6") (pintype "passive"))
    )
    (net (code "185") (name "unconnected-(UUTA-O-Pad1)") (class "Default")
      (node (ref "UUT") (pin "1") (pinfunction "O_1") (pintype "passive"))
    )
  )
)
